# sensor_matrix_01.net
KiCad netlist of a schematic drawn in Altium Designer
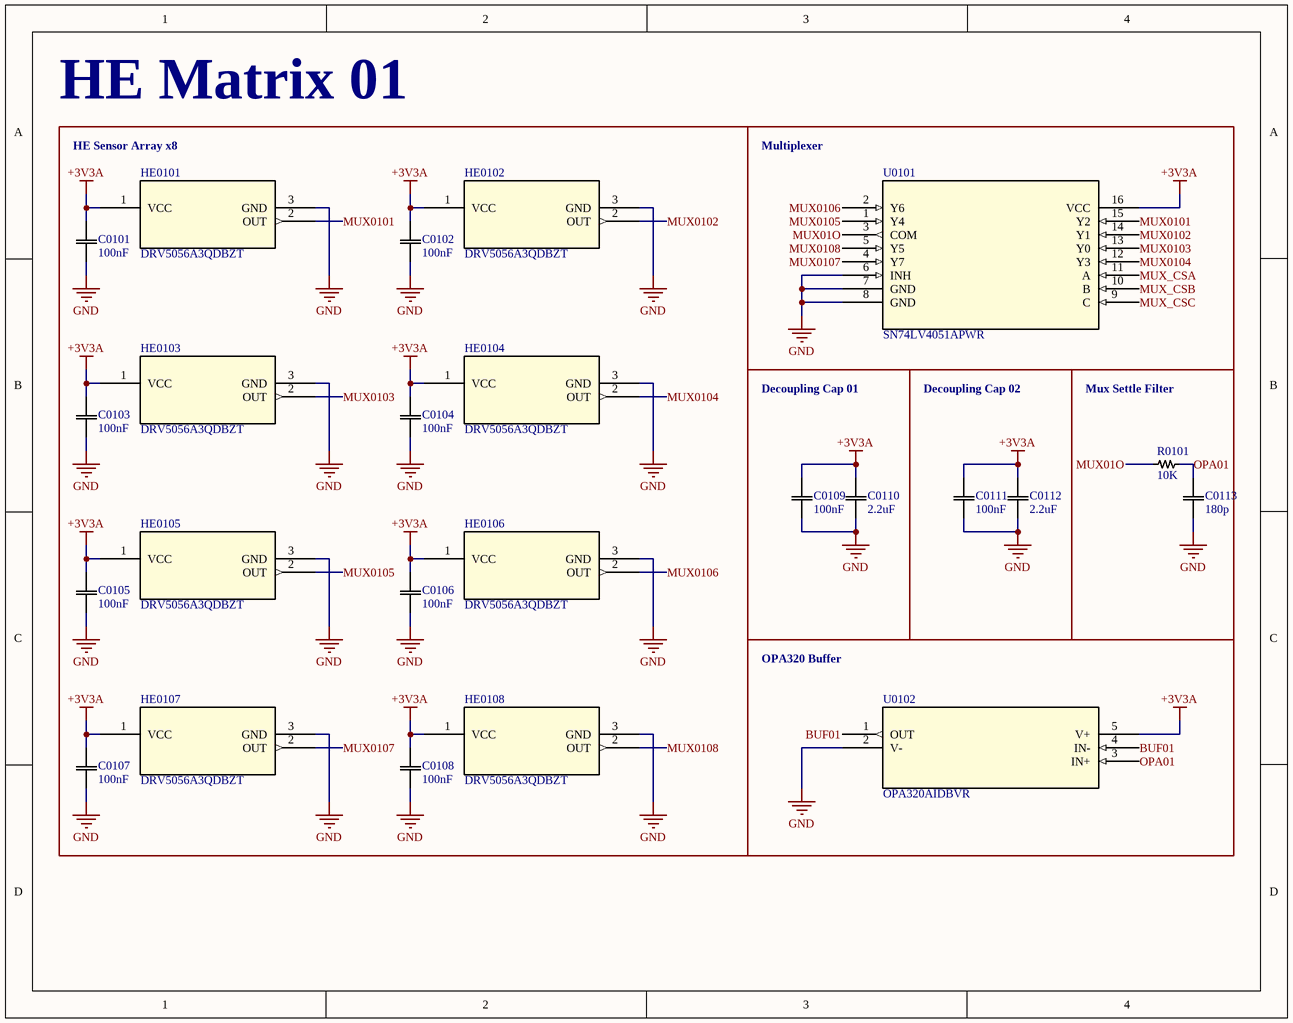
[diagram p0: sensor_matrix_01.SchDoc]

(export (version "E")
  (design (tool "Eeschema 10.0.6"))
  (components
    (comp (ref "C0101")
      (value "100nF")
      (footprint "CAPC10555_55N_KEM")
      (description "SMD Comm X7R, Ceramic, SMD, MLCC, Temperature Stable, 0402")
      (fields
        (field (name "MANUFACTURER_PART_NUMBER") "C0402C104K4RACTU")
        (field (name "COPYRIGHT") "Copyright (C) 2025 Ultra Librarian. All rights reserved.")
      )
      (libsource (lib "SplitHE_Int") (part "C0402"))
    )
    (comp (ref "C0102")
      (value "100nF")
      (footprint "CAPC10555_55N_KEM")
      (description "SMD Comm X7R, Ceramic, SMD, MLCC, Temperature Stable, 0402")
      (fields
        (field (name "MANUFACTURER_PART_NUMBER") "C0402C104K4RACTU")
        (field (name "COPYRIGHT") "Copyright (C) 2025 Ultra Librarian. All rights reserved.")
      )
      (libsource (lib "SplitHE_Int") (part "C0402"))
    )
    (comp (ref "C0103")
      (value "100nF")
      (footprint "CAPC10555_55N_KEM")
      (description "SMD Comm X7R, Ceramic, SMD, MLCC, Temperature Stable, 0402")
      (fields
        (field (name "MANUFACTURER_PART_NUMBER") "C0402C104K4RACTU")
        (field (name "COPYRIGHT") "Copyright (C) 2025 Ultra Librarian. All rights reserved.")
      )
      (libsource (lib "SplitHE_Int") (part "C0402"))
    )
    (comp (ref "C0104")
      (value "100nF")
      (footprint "CAPC10555_55N_KEM")
      (description "SMD Comm X7R, Ceramic, SMD, MLCC, Temperature Stable, 0402")
      (fields
        (field (name "MANUFACTURER_PART_NUMBER") "C0402C104K4RACTU")
        (field (name "COPYRIGHT") "Copyright (C) 2025 Ultra Librarian. All rights reserved.")
      )
      (libsource (lib "SplitHE_Int") (part "C0402"))
    )
    (comp (ref "C0105")
      (value "100nF")
      (footprint "CAPC10555_55N_KEM")
      (description "SMD Comm X7R, Ceramic, SMD, MLCC, Temperature Stable, 0402")
      (fields
        (field (name "MANUFACTURER_PART_NUMBER") "C0402C104K4RACTU")
        (field (name "COPYRIGHT") "Copyright (C) 2025 Ultra Librarian. All rights reserved.")
      )
      (libsource (lib "SplitHE_Int") (part "C0402"))
    )
    (comp (ref "C0106")
      (value "100nF")
      (footprint "CAPC10555_55N_KEM")
      (description "SMD Comm X7R, Ceramic, SMD, MLCC, Temperature Stable, 0402")
      (fields
        (field (name "MANUFACTURER_PART_NUMBER") "C0402C104K4RACTU")
        (field (name "COPYRIGHT") "Copyright (C) 2025 Ultra Librarian. All rights reserved.")
      )
      (libsource (lib "SplitHE_Int") (part "C0402"))
    )
    (comp (ref "C0107")
      (value "100nF")
      (footprint "CAPC10555_55N_KEM")
      (description "SMD Comm X7R, Ceramic, SMD, MLCC, Temperature Stable, 0402")
      (fields
        (field (name "MANUFACTURER_PART_NUMBER") "C0402C104K4RACTU")
        (field (name "COPYRIGHT") "Copyright (C) 2025 Ultra Librarian. All rights reserved.")
      )
      (libsource (lib "SplitHE_Int") (part "C0402"))
    )
    (comp (ref "C0108")
      (value "100nF")
      (footprint "CAPC10555_55N_KEM")
      (description "SMD Comm X7R, Ceramic, SMD, MLCC, Temperature Stable, 0402")
      (fields
        (field (name "MANUFACTURER_PART_NUMBER") "C0402C104K4RACTU")
        (field (name "COPYRIGHT") "Copyright (C) 2025 Ultra Librarian. All rights reserved.")
      )
      (libsource (lib "SplitHE_Int") (part "C0402"))
    )
    (comp (ref "C0109")
      (value "100nF")
      (footprint "CAPC10555_55N_KEM")
      (description "SMD Comm X7R, Ceramic, SMD, MLCC, Temperature Stable, 0402")
      (fields
        (field (name "MANUFACTURER_PART_NUMBER") "C0402C104K4RACTU")
        (field (name "COPYRIGHT") "Copyright (C) 2025 Ultra Librarian. All rights reserved.")
      )
      (libsource (lib "SplitHE_Int") (part "C0402"))
    )
    (comp (ref "C0110")
      (value "2.2uF")
      (footprint "CAPC10555_55N_KEM")
      (description "SMD Comm X7R, Ceramic, SMD, MLCC, Temperature Stable, 0402")
      (fields
        (field (name "MANUFACTURER_PART_NUMBER") "C0402C104K4RACTU")
        (field (name "COPYRIGHT") "Copyright (C) 2025 Ultra Librarian. All rights reserved.")
      )
      (libsource (lib "SplitHE_Int") (part "C0402"))
    )
    (comp (ref "C0111")
      (value "100nF")
      (footprint "CAPC10555_55N_KEM")
      (description "SMD Comm X7R, Ceramic, SMD, MLCC, Temperature Stable, 0402")
      (fields
        (field (name "MANUFACTURER_PART_NUMBER") "C0402C104K4RACTU")
        (field (name "COPYRIGHT") "Copyright (C) 2025 Ultra Librarian. All rights reserved.")
      )
      (libsource (lib "SplitHE_Int") (part "C0402"))
    )
    (comp (ref "C0112")
      (value "2.2uF")
      (footprint "CAPC10555_55N_KEM")
      (description "SMD Comm X7R, Ceramic, SMD, MLCC, Temperature Stable, 0402")
      (fields
        (field (name "MANUFACTURER_PART_NUMBER") "C0402C104K4RACTU")
        (field (name "COPYRIGHT") "Copyright (C) 2025 Ultra Librarian. All rights reserved.")
      )
      (libsource (lib "SplitHE_Int") (part "C0402"))
    )
    (comp (ref "C0113")
      (value "180p")
      (footprint "CAPC10555_55N_KEM")
      (description "SMD Comm X7R, Ceramic, SMD, MLCC, Temperature Stable, 0402")
      (fields
        (field (name "MANUFACTURER_PART_NUMBER") "C0402C104K4RACTU")
        (field (name "COPYRIGHT") "Copyright (C) 2025 Ultra Librarian. All rights reserved.")
      )
      (libsource (lib "SplitHE_Int") (part "C0402"))
    )
    (comp (ref "HE0101")
      (value "DRV5056A3QDBZT")
      (footprint "DBZ3_TEX")
      (description "Ratiometric unipolar linear hall effect sensor with analog output 3-SOT-23 -40 to 125")
      (fields (field (name "COPYRIGHT") "Copyright (C) 2025 Ultra Librarian. All rights reserved."))
      (libsource (lib "DRV5056A3QDBZT") (part "DRV5056A3QDBZT"))
    )
    (comp (ref "HE0102")
      (value "DRV5056A3QDBZT")
      (footprint "DBZ3_TEX")
      (description "Ratiometric unipolar linear hall effect sensor with analog output 3-SOT-23 -40 to 125")
      (fields (field (name "COPYRIGHT") "Copyright (C) 2025 Ultra Librarian. All rights reserved."))
      (libsource (lib "DRV5056A3QDBZT") (part "DRV5056A3QDBZT"))
    )
    (comp (ref "HE0103")
      (value "DRV5056A3QDBZT")
      (footprint "DBZ3_TEX")
      (description "Ratiometric unipolar linear hall effect sensor with analog output 3-SOT-23 -40 to 125")
      (fields (field (name "COPYRIGHT") "Copyright (C) 2025 Ultra Librarian. All rights reserved."))
      (libsource (lib "DRV5056A3QDBZT") (part "DRV5056A3QDBZT"))
    )
    (comp (ref "HE0104")
      (value "DRV5056A3QDBZT")
      (footprint "DBZ3_TEX")
      (description "Ratiometric unipolar linear hall effect sensor with analog output 3-SOT-23 -40 to 125")
      (fields (field (name "COPYRIGHT") "Copyright (C) 2025 Ultra Librarian. All rights reserved."))
      (libsource (lib "DRV5056A3QDBZT") (part "DRV5056A3QDBZT"))
    )
    (comp (ref "HE0105")
      (value "DRV5056A3QDBZT")
      (footprint "DBZ3_TEX")
      (description "Ratiometric unipolar linear hall effect sensor with analog output 3-SOT-23 -40 to 125")
      (fields (field (name "COPYRIGHT") "Copyright (C) 2025 Ultra Librarian. All rights reserved."))
      (libsource (lib "DRV5056A3QDBZT") (part "DRV5056A3QDBZT"))
    )
    (comp (ref "HE0106")
      (value "DRV5056A3QDBZT")
      (footprint "DBZ3_TEX")
      (description "Ratiometric unipolar linear hall effect sensor with analog output 3-SOT-23 -40 to 125")
      (fields (field (name "COPYRIGHT") "Copyright (C) 2025 Ultra Librarian. All rights reserved."))
      (libsource (lib "DRV5056A3QDBZT") (part "DRV5056A3QDBZT"))
    )
    (comp (ref "HE0107")
      (value "DRV5056A3QDBZT")
      (footprint "DBZ3_TEX")
      (description "Ratiometric unipolar linear hall effect sensor with analog output 3-SOT-23 -40 to 125")
      (fields (field (name "COPYRIGHT") "Copyright (C) 2025 Ultra Librarian. All rights reserved."))
      (libsource (lib "DRV5056A3QDBZT") (part "DRV5056A3QDBZT"))
    )
    (comp (ref "HE0108")
      (value "DRV5056A3QDBZT")
      (footprint "DBZ3_TEX")
      (description "Ratiometric unipolar linear hall effect sensor with analog output 3-SOT-23 -40 to 125")
      (fields (field (name "COPYRIGHT") "Copyright (C) 2025 Ultra Librarian. All rights reserved."))
      (libsource (lib "DRV5056A3QDBZT") (part "DRV5056A3QDBZT"))
    )
    (comp (ref "R0101")
      (value "10K")
      (footprint "RES0402_CPF_TYCO_TYC")
      (description "CPF 0402 RL")
      (fields
        (field (name "MANUFACTURER_PART_NUMBER") "CPF0402B33RE1")
        (field (name "COPYRIGHT") "Copyright (C) 2025 Ultra Librarian. All rights reserved.")
      )
      (libsource (lib "SplitHE_Int") (part "R0402"))
    )
    (comp (ref "U0101")
      (value "SN74LV4051APWR")
      (footprint "PW16")
      (description "5V 8:1 one-channel general-purpose analog multiplexer 16-TSSOP -40 to 85")
      (fields (field (name "COPYRIGHT") "Copyright (C) 2025 Ultra Librarian. All rights reserved."))
      (libsource (lib "SN74LV4051APWR") (part "SN74LV4051APWR"))
    )
    (comp (ref "U0102")
      (value "OPA320AIDBVR")
      (footprint "DBV5")
      (description "Precision, zero-crossover, 20-MHz, 0.9-pA Ib, RRIO, CMOS operational amplifier 5-SOT-23 -40 to 125")
      (fields (field (name "COPYRIGHT") "Copyright (C) 2025 Ultra Librarian. All rights reserved."))
      (libsource (lib "OPA320AIDBVR") (part "OPA320AIDBVR"))
    )
  )
  (nets
    (net (code "1") (name "+3V3A") (class "Default")
      (node (ref "C0101") (pin "2") (pinfunction "2_2") (pintype "passive"))
      (node (ref "C0102") (pin "2") (pinfunction "2_2") (pintype "passive"))
      (node (ref "C0103") (pin "2") (pinfunction "2_2") (pintype "passive"))
      (node (ref "C0104") (pin "2") (pinfunction "2_2") (pintype "passive"))
      (node (ref "C0105") (pin "2") (pinfunction "2_2") (pintype "passive"))
      (node (ref "C0106") (pin "2") (pinfunction "2_2") (pintype "passive"))
      (node (ref "C0107") (pin "2") (pinfunction "2_2") (pintype "passive"))
      (node (ref "C0108") (pin "2") (pinfunction "2_2") (pintype "passive"))
      (node (ref "C0109") (pin "2") (pinfunction "2_2") (pintype "passive"))
      (node (ref "C0110") (pin "2") (pinfunction "2_2") (pintype "passive"))
      (node (ref "C0111") (pin "2") (pinfunction "2_2") (pintype "passive"))
      (node (ref "C0112") (pin "2") (pinfunction "2_2") (pintype "passive"))
      (node (ref "HE0101") (pin "1") (pinfunction "VCC_1") (pintype "power_in"))
      (node (ref "HE0102") (pin "1") (pinfunction "VCC_1") (pintype "power_in"))
      (node (ref "HE0103") (pin "1") (pinfunction "VCC_1") (pintype "power_in"))
      (node (ref "HE0104") (pin "1") (pinfunction "VCC_1") (pintype "power_in"))
      (node (ref "HE0105") (pin "1") (pinfunction "VCC_1") (pintype "power_in"))
      (node (ref "HE0106") (pin "1") (pinfunction "VCC_1") (pintype "power_in"))
      (node (ref "HE0107") (pin "1") (pinfunction "VCC_1") (pintype "power_in"))
      (node (ref "HE0108") (pin "1") (pinfunction "VCC_1") (pintype "power_in"))
      (node (ref "U0101") (pin "16") (pinfunction "VCC_16") (pintype "power_in"))
      (node (ref "U0102") (pin "5") (pinfunction "V+_5") (pintype "power_in"))
    )
    (net (code "2") (name "/BUF01") (class "Default")
      (node (ref "U0102") (pin "1") (pinfunction "OUT_1") (pintype "output"))
      (node (ref "U0102") (pin "4") (pinfunction "IN-_4") (pintype "input"))
    )
    (net (code "3") (name "/MUX01O") (class "Default")
      (node (ref "R0101") (pin "2") (pinfunction "2_2") (pintype "passive"))
      (node (ref "U0101") (pin "3") (pinfunction "COM_3") (pintype "output"))
    )
    (net (code "4") (name "/MUX0101") (class "Default")
      (node (ref "HE0101") (pin "2") (pinfunction "OUT_2") (pintype "output"))
      (node (ref "U0101") (pin "15") (pinfunction "Y2_15") (pintype "input"))
    )
    (net (code "5") (name "/MUX0102") (class "Default")
      (node (ref "HE0102") (pin "2") (pinfunction "OUT_2") (pintype "output"))
      (node (ref "U0101") (pin "14") (pinfunction "Y1_14") (pintype "input"))
    )
    (net (code "6") (name "/MUX0103") (class "Default")
      (node (ref "HE0103") (pin "2") (pinfunction "OUT_2") (pintype "output"))
      (node (ref "U0101") (pin "13") (pinfunction "Y0_13") (pintype "input"))
    )
    (net (code "7") (name "/MUX0104") (class "Default")
      (node (ref "HE0104") (pin "2") (pinfunction "OUT_2") (pintype "output"))
      (node (ref "U0101") (pin "12") (pinfunction "Y3_12") (pintype "input"))
    )
    (net (code "8") (name "/MUX0105") (class "Default")
      (node (ref "HE0105") (pin "2") (pinfunction "OUT_2") (pintype "output"))
      (node (ref "U0101") (pin "1") (pinfunction "Y4_1") (pintype "input"))
    )
    (net (code "9") (name "/MUX0106") (class "Default")
      (node (ref "HE0106") (pin "2") (pinfunction "OUT_2") (pintype "output"))
      (node (ref "U0101") (pin "2") (pinfunction "Y6_2") (pintype "input"))
    )
    (net (code "10") (name "/MUX0107") (class "Default")
      (node (ref "HE0107") (pin "2") (pinfunction "OUT_2") (pintype "output"))
      (node (ref "U0101") (pin "4") (pinfunction "Y7_4") (pintype "input"))
    )
    (net (code "11") (name "/MUX0108") (class "Default")
      (node (ref "HE0108") (pin "2") (pinfunction "OUT_2") (pintype "output"))
      (node (ref "U0101") (pin "5") (pinfunction "Y5_5") (pintype "input"))
    )
    (net (code "12") (name "/MUX_CSA") (class "Default")
      (node (ref "U0101") (pin "11") (pinfunction "A_11") (pintype "input"))
    )
    (net (code "13") (name "/MUX_CSB") (class "Default")
      (node (ref "U0101") (pin "10") (pinfunction "B_10") (pintype "input"))
    )
    (net (code "14") (name "/MUX_CSC") (class "Default")
      (node (ref "U0101") (pin "9") (pinfunction "C_9") (pintype "input"))
    )
    (net (code "15") (name "/OPA01") (class "Default")
      (node (ref "C0113") (pin "2") (pinfunction "2_2") (pintype "passive"))
      (node (ref "R0101") (pin "1") (pinfunction "1_1") (pintype "passive"))
      (node (ref "U0102") (pin "3") (pinfunction "IN+_3") (pintype "input"))
    )
    (net (code "16") (name "GND") (class "Default")
      (node (ref "C0101") (pin "1") (pinfunction "1_1") (pintype "passive"))
      (node (ref "C0102") (pin "1") (pinfunction "1_1") (pintype "passive"))
      (node (ref "C0103") (pin "1") (pinfunction "1_1") (pintype "passive"))
      (node (ref "C0104") (pin "1") (pinfunction "1_1") (pintype "passive"))
      (node (ref "C0105") (pin "1") (pinfunction "1_1") (pintype "passive"))
      (node (ref "C0106") (pin "1") (pinfunction "1_1") (pintype "passive"))
      (node (ref "C0107") (pin "1") (pinfunction "1_1") (pintype "passive"))
      (node (ref "C0108") (pin "1") (pinfunction "1_1") (pintype "passive"))
      (node (ref "C0109") (pin "1") (pinfunction "1_1") (pintype "passive"))
      (node (ref "C0110") (pin "1") (pinfunction "1_1") (pintype "passive"))
      (node (ref "C0111") (pin "1") (pinfunction "1_1") (pintype "passive"))
      (node (ref "C0112") (pin "1") (pinfunction "1_1") (pintype "passive"))
      (node (ref "C0113") (pin "1") (pinfunction "1_1") (pintype "passive"))
      (node (ref "HE0101") (pin "3") (pinfunction "GND_3") (pintype "power_in"))
      (node (ref "HE0102") (pin "3") (pinfunction "GND_3") (pintype "power_in"))
      (node (ref "HE0103") (pin "3") (pinfunction "GND_3") (pintype "power_in"))
      (node (ref "HE0104") (pin "3") (pinfunction "GND_3") (pintype "power_in"))
      (node (ref "HE0105") (pin "3") (pinfunction "GND_3") (pintype "power_in"))
      (node (ref "HE0106") (pin "3") (pinfunction "GND_3") (pintype "power_in"))
      (node (ref "HE0107") (pin "3") (pinfunction "GND_3") (pintype "power_in"))
      (node (ref "HE0108") (pin "3") (pinfunction "GND_3") (pintype "power_in"))
      (node (ref "U0101") (pin "6") (pinfunction "INH_6") (pintype "input"))
      (node (ref "U0101") (pin "7") (pinfunction "GND_7") (pintype "power_in"))
      (node (ref "U0101") (pin "8") (pinfunction "GND_8") (pintype "power_in"))
      (node (ref "U0102") (pin "2") (pinfunction "V-_2") (pintype "power_in"))
    )
  )
)
